# DE-140824.net
KiCad netlist of a schematic drawn in Altium Designer
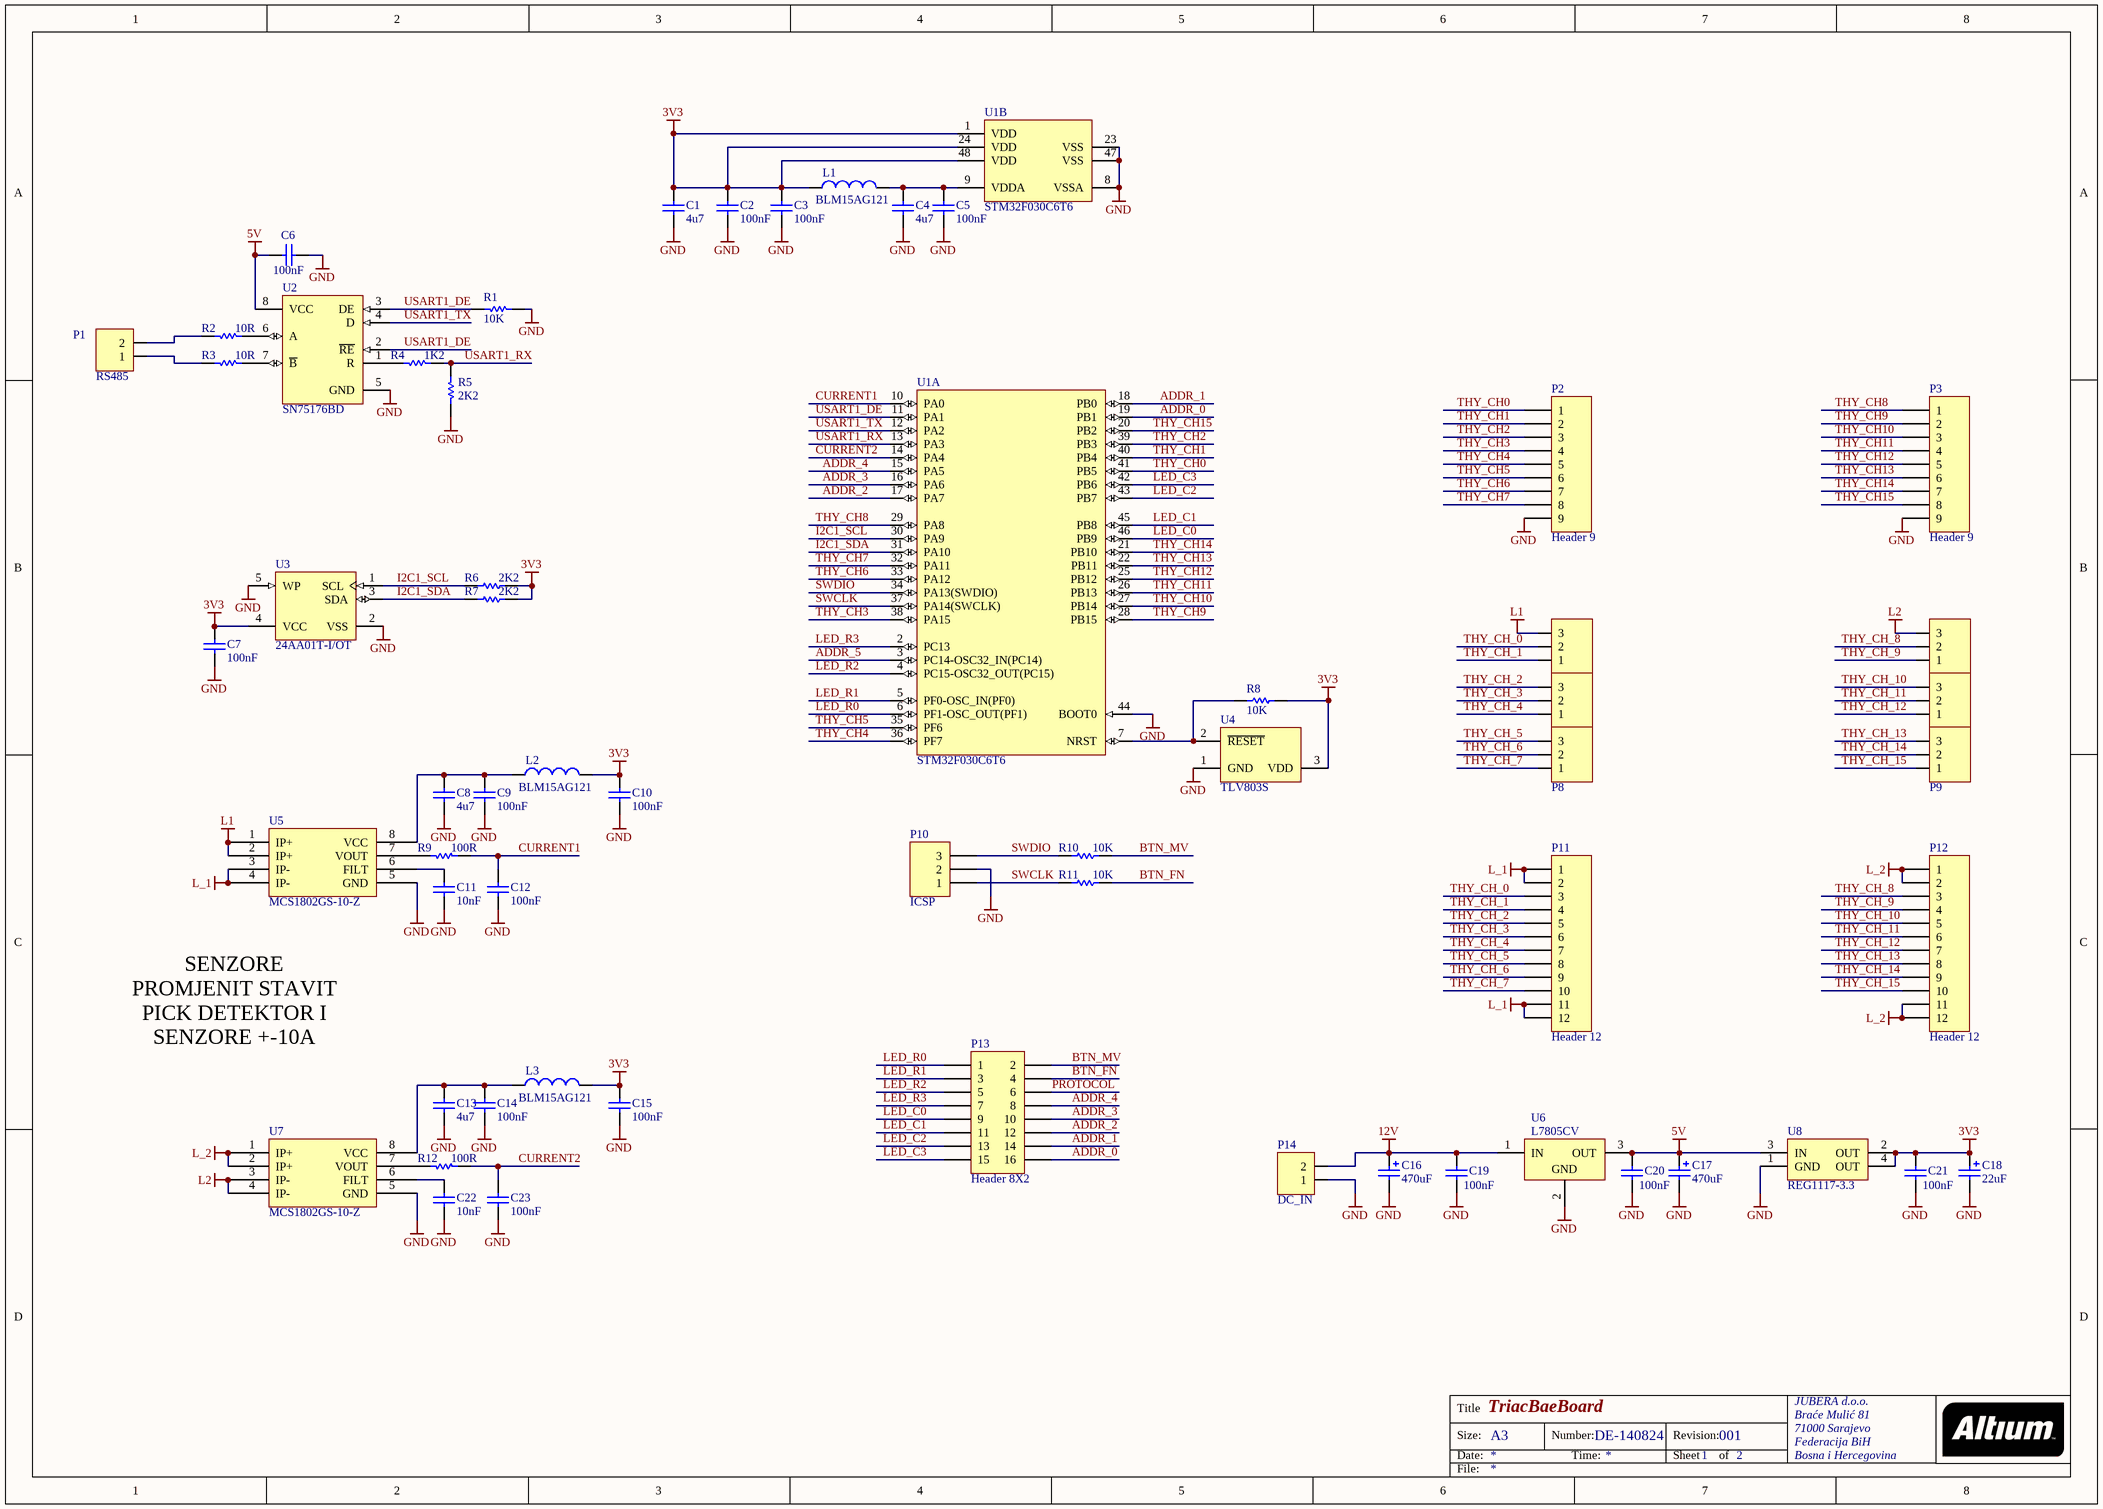
[diagram p0: DE-140824.SchDoc]

(export (version "E")
  (design (tool "Eeschema 10.0.6"))
  (components
    (comp (ref "C1")
      (value "4u7")
      (footprint "0805")
      (description "Ceramic Chip Capacitor - Standard")
      (fields (field (name "Comment") "C0805") (field (name "PUBLISHER") "Altium Limited"))
      (libsource (lib "DE-120824") (part "C0805"))
    )
    (comp (ref "C2")
      (value "100nF")
      (footprint "0603")
      (description "Ceramic Chip Capacitor - Standard")
      (fields (field (name "Comment") "C0603") (field (name "PUBLISHER") "Altium Limited"))
      (libsource (lib "DE-120824") (part "C0603"))
    )
    (comp (ref "C3")
      (value "100nF")
      (footprint "0603")
      (description "Ceramic Chip Capacitor - Standard")
      (fields (field (name "Comment") "C0603") (field (name "PUBLISHER") "Altium Limited"))
      (libsource (lib "DE-120824") (part "C0603"))
    )
    (comp (ref "C4")
      (value "4u7")
      (footprint "0805")
      (description "Ceramic Chip Capacitor - Standard")
      (fields (field (name "Comment") "C0805") (field (name "PUBLISHER") "Altium Limited"))
      (libsource (lib "DE-120824") (part "C0805"))
    )
    (comp (ref "C5")
      (value "100nF")
      (footprint "0603")
      (description "Ceramic Chip Capacitor - Standard")
      (fields (field (name "Comment") "C0603") (field (name "PUBLISHER") "Altium Limited"))
      (libsource (lib "DE-120824") (part "C0603"))
    )
    (comp (ref "C6")
      (value "100nF")
      (footprint "0603")
      (description "Ceramic Chip Capacitor - Standard")
      (fields (field (name "PUBLISHER") "Altium Limited"))
      (libsource (lib "DE-220817") (part "C0603"))
    )
    (comp (ref "C7")
      (value "100nF")
      (footprint "0603")
      (description "Ceramic Chip Capacitor - Standard")
      (fields (field (name "Comment") "C0603") (field (name "PUBLISHER") "Altium Limited"))
      (libsource (lib "DE-120824") (part "C0603"))
    )
    (comp (ref "C8")
      (value "4u7")
      (footprint "0805")
      (description "Ceramic Chip Capacitor - Standard")
      (fields (field (name "Comment") "C0805") (field (name "PUBLISHER") "Altium Limited"))
      (libsource (lib "DE-120824") (part "C0805"))
    )
    (comp (ref "C9")
      (value "100nF")
      (footprint "0603")
      (description "Ceramic Chip Capacitor - Standard")
      (fields (field (name "Comment") "C0603") (field (name "PUBLISHER") "Altium Limited"))
      (libsource (lib "DE-120824") (part "C0603"))
    )
    (comp (ref "C10")
      (value "100nF")
      (footprint "0603")
      (description "Ceramic Chip Capacitor - Standard")
      (fields (field (name "Comment") "C0603") (field (name "PUBLISHER") "Altium Limited"))
      (libsource (lib "DE-120824") (part "C0603"))
    )
    (comp (ref "C11")
      (value "10nF")
      (footprint "0603")
      (description "Ceramic Chip Capacitor - Standard")
      (fields (field (name "Comment") "C0603") (field (name "PUBLISHER") "Altium Limited"))
      (libsource (lib "DE-120824") (part "C0603"))
    )
    (comp (ref "C12")
      (value "100nF")
      (footprint "0603")
      (description "Ceramic Chip Capacitor - Standard")
      (fields (field (name "Comment") "C0603") (field (name "PUBLISHER") "Altium Limited"))
      (libsource (lib "DE-120824") (part "C0603"))
    )
    (comp (ref "C13")
      (value "4u7")
      (footprint "0805")
      (description "Ceramic Chip Capacitor - Standard")
      (fields (field (name "Comment") "C0805") (field (name "PUBLISHER") "Altium Limited"))
      (libsource (lib "DE-120824") (part "C0805"))
    )
    (comp (ref "C14")
      (value "100nF")
      (footprint "0603")
      (description "Ceramic Chip Capacitor - Standard")
      (fields (field (name "Comment") "C0603") (field (name "PUBLISHER") "Altium Limited"))
      (libsource (lib "DE-120824") (part "C0603"))
    )
    (comp (ref "C15")
      (value "100nF")
      (footprint "0603")
      (description "Ceramic Chip Capacitor - Standard")
      (fields (field (name "Comment") "C0603") (field (name "PUBLISHER") "Altium Limited"))
      (libsource (lib "DE-120824") (part "C0603"))
    )
    (comp (ref "C16")
      (value "470uF")
      (footprint "CAPPR5-10X12.5")
      (description "Aluminum Electrolytic Capacitor, Radial Style with Long Leads: 470uF, 25V")
      (fields (field (name "PUBLISHER") "Altium Limited"))
      (libsource (lib "DE-010824") (part "EKA00DC347E00"))
    )
    (comp (ref "C17")
      (value "470uF")
      (footprint "CAPPR5-10X12.5")
      (description "Aluminum Electrolytic Capacitor, Radial Style with Long Leads: 470uF, 25V")
      (fields (field (name "PUBLISHER") "Altium Limited"))
      (libsource (lib "DE-010824") (part "EKA00DC347E00"))
    )
    (comp (ref "C18")
      (value "22uF")
      (footprint "CAPPR2-5X11")
      (description "Aluminum Electrolytic Capacitor, Radial Style with Long Leads: 47uF, 35V")
      (fields (field (name "PUBLISHER") "Altium Limited"))
      (libsource (lib "DE-010824") (part "EKA00AA247F00"))
    )
    (comp (ref "C19")
      (value "100nF")
      (footprint "0603")
      (description "Ceramic Chip Capacitor - Standard")
      (fields (field (name "PUBLISHER") "Altium Limited"))
      (libsource (lib "DE-220817") (part "C0603"))
    )
    (comp (ref "C20")
      (value "100nF")
      (footprint "0603")
      (description "Ceramic Chip Capacitor - Standard")
      (fields (field (name "PUBLISHER") "Altium Limited"))
      (libsource (lib "DE-220817") (part "C0603"))
    )
    (comp (ref "C21")
      (value "100nF")
      (footprint "0603")
      (description "Ceramic Chip Capacitor - Standard")
      (fields (field (name "PUBLISHER") "Altium Limited"))
      (libsource (lib "DE-220817") (part "C0603"))
    )
    (comp (ref "C22")
      (value "10nF")
      (footprint "0603")
      (description "Ceramic Chip Capacitor - Standard")
      (fields (field (name "Comment") "C0603") (field (name "PUBLISHER") "Altium Limited"))
      (libsource (lib "DE-120824") (part "C0603"))
    )
    (comp (ref "C23")
      (value "100nF")
      (footprint "0603")
      (description "Ceramic Chip Capacitor - Standard")
      (fields (field (name "Comment") "C0603") (field (name "PUBLISHER") "Altium Limited"))
      (libsource (lib "DE-120824") (part "C0603"))
    )
    (comp (ref "L1")
      (value "BLM15AG121")
      (footprint "0402-A")
      (description "SMD chip inductor")
      (fields (field (name "PUBLISHER") "Altium Limited"))
      (libsource (lib "DE-120824") (part "Chip inductor"))
    )
    (comp (ref "L2")
      (value "BLM15AG121")
      (footprint "0402-A")
      (description "SMD chip inductor")
      (fields (field (name "PUBLISHER") "Altium Limited"))
      (libsource (lib "DE-120824") (part "Chip inductor"))
    )
    (comp (ref "L3")
      (value "BLM15AG121")
      (footprint "0402-A")
      (description "SMD chip inductor")
      (fields (field (name "PUBLISHER") "Altium Limited"))
      (libsource (lib "DE-120824") (part "Chip inductor"))
    )
    (comp (ref "P1")
      (value "RS485")
      (footprint "TERMINAL BLOK 2")
      (description "Terminal blok konektor 3,5 mm")
      (libsource (lib "DE-120824") (part "TERMINAL BLOK 2"))
    )
    (comp (ref "P2")
      (value "Header 9")
      (footprint "HDR1X9")
      (description "Header, 9-Pin")
      (fields (field (name "PUBLISHER") "Altium Limited"))
      (libsource (lib "Miscellaneous Connectors") (part "Header 9"))
    )
    (comp (ref "P3")
      (value "Header 9")
      (footprint "HDR1X9")
      (description "Header, 9-Pin")
      (fields (field (name "PUBLISHER") "Altium Limited"))
      (libsource (lib "Miscellaneous Connectors") (part "Header 9"))
    )
    (comp (ref "P4")
      (value "~")
      (footprint "TERMINAL BLOK 3")
      (description "3 pinski terminal blok konektor")
      (libsource (lib "DE-120824") (part "TERMINAL BLOK 3"))
    )
    (comp (ref "P5")
      (value "~")
      (footprint "TERMINAL BLOK 3")
      (description "3 pinski terminal blok konektor")
      (libsource (lib "DE-120824") (part "TERMINAL BLOK 3"))
    )
    (comp (ref "P6")
      (value "~")
      (footprint "TERMINAL BLOK 3")
      (description "3 pinski terminal blok konektor")
      (libsource (lib "DE-120824") (part "TERMINAL BLOK 3"))
    )
    (comp (ref "P7")
      (value "~")
      (footprint "TERMINAL BLOK 3")
      (description "3 pinski terminal blok konektor")
      (libsource (lib "DE-120824") (part "TERMINAL BLOK 3"))
    )
    (comp (ref "P8")
      (value "~")
      (footprint "TERMINAL BLOK 3")
      (description "3 pinski terminal blok konektor")
      (libsource (lib "DE-120824") (part "TERMINAL BLOK 3"))
    )
    (comp (ref "P9")
      (value "~")
      (footprint "TERMINAL BLOK 3")
      (description "3 pinski terminal blok konektor")
      (libsource (lib "DE-120824") (part "TERMINAL BLOK 3"))
    )
    (comp (ref "P10")
      (value "ICSP")
      (footprint "HDR1X3")
      (description "Header, 3-Pin")
      (fields (field (name "PUBLISHER") "Altium Limited"))
      (libsource (lib "Miscellaneous Connectors") (part "Header 3"))
    )
    (comp (ref "P11")
      (value "Header 12")
      (footprint "HDR1X12")
      (description "Header, 12-Pin")
      (fields (field (name "PUBLISHER") "Altium Limited"))
      (libsource (lib "Miscellaneous Connectors") (part "Header 12"))
    )
    (comp (ref "P12")
      (value "Header 12")
      (footprint "HDR1X12")
      (description "Header, 12-Pin")
      (fields (field (name "PUBLISHER") "Altium Limited"))
      (libsource (lib "Miscellaneous Connectors") (part "Header 12"))
    )
    (comp (ref "P13")
      (value "Header 8X2")
      (footprint "HDR2X8")
      (description "Header, 8-Pin, Dual row")
      (fields (field (name "PUBLISHER") "Altium Limited"))
      (libsource (lib "Miscellaneous Connectors") (part "Header 8X2"))
    )
    (comp (ref "P14")
      (value "DC_IN")
      (footprint "TERMINAL BLOK 2")
      (description "Terminal blok konektor 3,5 mm")
      (libsource (lib "DE-010824") (part "TERMINAL BLOK 2"))
    )
    (comp (ref "R1")
      (value "10K")
      (footprint "ERA-0603")
      (fields (field (name "PUBLISHER") "Altium Limited"))
      (libsource (lib "DE-220817") (part "ERAV"))
    )
    (comp (ref "R2")
      (value "10R")
      (footprint "ERA-0603")
      (fields (field (name "PUBLISHER") "Altium Limited"))
      (libsource (lib "DE-220817") (part "ERAV"))
    )
    (comp (ref "R3")
      (value "10R")
      (footprint "ERA-0603")
      (fields (field (name "PUBLISHER") "Altium Limited"))
      (libsource (lib "DE-220817") (part "ERAV"))
    )
    (comp (ref "R4")
      (value "1K2")
      (footprint "ERA-0603")
      (fields (field (name "PUBLISHER") "Altium Limited"))
      (libsource (lib "DE-220817") (part "ERAV"))
    )
    (comp (ref "R5")
      (value "2K2")
      (footprint "ERA-0603")
      (fields (field (name "PUBLISHER") "Altium Limited"))
      (libsource (lib "DE-220817") (part "ERAV"))
    )
    (comp (ref "R6")
      (value "2K2")
      (footprint "ERA-0603")
      (fields (field (name "PUBLISHER") "Altium Limited"))
      (libsource (lib "DE-120824") (part "ERA3Y"))
    )
    (comp (ref "R7")
      (value "2K2")
      (footprint "ERA-0603")
      (fields (field (name "PUBLISHER") "Altium Limited"))
      (libsource (lib "DE-120824") (part "ERA3Y"))
    )
    (comp (ref "R8")
      (value "10K")
      (footprint "ERA-0603")
      (fields (field (name "PUBLISHER") "Altium Limited"))
      (libsource (lib "DE-120824") (part "ERA3Y"))
    )
    (comp (ref "R9")
      (value "100R")
      (footprint "ERA-0603")
      (fields (field (name "PUBLISHER") "Altium Limited"))
      (libsource (lib "DE-220817") (part "ERAV"))
    )
    (comp (ref "R10")
      (value "10K")
      (footprint "ERA-0603")
      (fields (field (name "PUBLISHER") "Altium Limited"))
      (libsource (lib "DE-120824") (part "ERA3Y"))
    )
    (comp (ref "R11")
      (value "10K")
      (footprint "ERA-0603")
      (fields (field (name "PUBLISHER") "Altium Limited"))
      (libsource (lib "DE-120824") (part "ERA3Y"))
    )
    (comp (ref "R12")
      (value "100R")
      (footprint "ERA-0603")
      (fields (field (name "PUBLISHER") "Altium Limited"))
      (libsource (lib "DE-220817") (part "ERAV"))
    )
    (comp (ref "U1")
      (value "STM32F030C6T6")
      (footprint "STM-LQFP48_N")
      (libsource (lib "STMicroelectronics STM32 F0") (part "STM32F030C6T6"))
    )
    (comp (ref "U2")
      (value "SN75176BD")
      (footprint "D008_N")
      (description "Differential Bus Transceiver")
      (fields (field (name "PUBLISHER") "Altium Limited"))
      (libsource (lib "DE-010824") (part "SN75176BD"))
    )
    (comp (ref "U3")
      (value "24AA01T-I/OT")
      (footprint "SOT-23-OT5_N")
      (description "1Kbit, 400kHz, 1.8V, I2C Serial EEPROM, 5-Pin SOT-23, Industrial Temperature, Tape and Reel")
      (fields (field (name "PUBLISHER") "Altium Limited"))
      (libsource (lib "Microchip Memory I2C Serial EEPROM") (part "24AA01T-I/OT"))
    )
    (comp (ref "U4")
      (value "TLV803S")
      (footprint "DBZ3_N")
      (fields (field (name "MANUFACTURER") "Texas Instruments") (field (name "PARTNUMBER") "TLV803MDBZR"))
      (libsource (lib "TI Power Management Supervisor and Reset IC") (part "TLV803MDBZR"))
    )
    (comp (ref "U5")
      (value "MCS1802GS-10-Z")
      (footprint "SOIC-SN8_N")
      (libsource (lib "DE-120824") (part "ACS71240"))
    )
    (comp (ref "U6")
      (value "L7805CV")
      (footprint "TO220")
      (description "Positive Voltage Regulator, 5V, 3-Pin TO-220")
      (libsource (lib "DE-010824") (part "L7805CV"))
    )
    (comp (ref "U7")
      (value "MCS1802GS-10-Z")
      (footprint "SOIC-SN8_N")
      (libsource (lib "DE-120824") (part "ACS71240"))
    )
    (comp (ref "U8")
      (value "REG1117-3.3")
      (footprint "ZZ311")
      (description "800mA and 1A Low Dropout Positive Regulator 2.85V, 3.3V, 5V, and Adjustable")
      (fields (field (name "PUBLISHER") "Altium Limited"))
      (libsource (lib "DE-010824") (part "REG1117-3.3"))
    )
  )
  (nets
    (net (code "1") (name "/ADDR_0") (class "Default")
      (node (ref "P13") (pin "16") (pinfunction "16_16") (pintype "passive"))
      (node (ref "U1") (pin "19") (pinfunction "PB1_19") (pintype "bidirectional"))
    )
    (net (code "2") (name "/ADDR_1") (class "Default")
      (node (ref "P13") (pin "14") (pinfunction "14_14") (pintype "passive"))
      (node (ref "U1") (pin "18") (pinfunction "PB0_18") (pintype "bidirectional"))
    )
    (net (code "3") (name "/ADDR_2") (class "Default")
      (node (ref "P13") (pin "12") (pinfunction "12_12") (pintype "passive"))
      (node (ref "U1") (pin "17") (pinfunction "PA7_17") (pintype "bidirectional"))
    )
    (net (code "4") (name "/ADDR_3") (class "Default")
      (node (ref "P13") (pin "10") (pinfunction "10_10") (pintype "passive"))
      (node (ref "U1") (pin "16") (pinfunction "PA6_16") (pintype "bidirectional"))
    )
    (net (code "5") (name "/ADDR_4") (class "Default")
      (node (ref "P13") (pin "8") (pinfunction "8_8") (pintype "passive"))
      (node (ref "U1") (pin "15") (pinfunction "PA5_15") (pintype "bidirectional"))
    )
    (net (code "6") (name "/ADDR_5") (class "Default")
      (node (ref "U1") (pin "3") (pinfunction "PC14-OSC32_IN(PC14)_3") (pintype "bidirectional"))
    )
    (net (code "7") (name "/BTN_FN") (class "Default")
      (node (ref "P13") (pin "4") (pinfunction "4_4") (pintype "passive"))
      (node (ref "R11") (pin "2") (pinfunction "2_2") (pintype "passive"))
    )
    (net (code "8") (name "/BTN_MV") (class "Default")
      (node (ref "P13") (pin "2") (pinfunction "2_2") (pintype "passive"))
      (node (ref "R10") (pin "2") (pinfunction "2_2") (pintype "passive"))
    )
    (net (code "9") (name "/CURRENT1") (class "Default")
      (node (ref "C12") (pin "2") (pinfunction "2_2") (pintype "passive"))
      (node (ref "R9") (pin "1") (pinfunction "1_1") (pintype "passive"))
      (node (ref "U1") (pin "10") (pinfunction "PA0_10") (pintype "bidirectional"))
    )
    (net (code "10") (name "/CURRENT2") (class "Default")
      (node (ref "C23") (pin "2") (pinfunction "2_2") (pintype "passive"))
      (node (ref "R12") (pin "1") (pinfunction "1_1") (pintype "passive"))
      (node (ref "U1") (pin "14") (pinfunction "PA4_14") (pintype "bidirectional"))
    )
    (net (code "11") (name "/I2C1_SCL") (class "Default")
      (node (ref "R6") (pin "1") (pinfunction "1_1") (pintype "passive"))
      (node (ref "U1") (pin "30") (pinfunction "PA9_30") (pintype "bidirectional"))
      (node (ref "U3") (pin "1") (pinfunction "SCL_1") (pintype "input"))
    )
    (net (code "12") (name "/I2C1_SDA") (class "Default")
      (node (ref "R7") (pin "1") (pinfunction "1_1") (pintype "passive"))
      (node (ref "U1") (pin "31") (pinfunction "PA10_31") (pintype "bidirectional"))
      (node (ref "U3") (pin "3") (pinfunction "SDA_3") (pintype "bidirectional"))
    )
    (net (code "13") (name "/LED_C0") (class "Default")
      (node (ref "P13") (pin "9") (pinfunction "9_9") (pintype "passive"))
      (node (ref "U1") (pin "46") (pinfunction "PB9_46") (pintype "bidirectional"))
    )
    (net (code "14") (name "/LED_C1") (class "Default")
      (node (ref "P13") (pin "11") (pinfunction "11_11") (pintype "passive"))
      (node (ref "U1") (pin "45") (pinfunction "PB8_45") (pintype "bidirectional"))
    )
    (net (code "15") (name "/LED_C2") (class "Default")
      (node (ref "P13") (pin "13") (pinfunction "13_13") (pintype "passive"))
      (node (ref "U1") (pin "43") (pinfunction "PB7_43") (pintype "bidirectional"))
    )
    (net (code "16") (name "/LED_C3") (class "Default")
      (node (ref "P13") (pin "15") (pinfunction "15_15") (pintype "passive"))
      (node (ref "U1") (pin "42") (pinfunction "PB6_42") (pintype "bidirectional"))
    )
    (net (code "17") (name "/LED_R0") (class "Default")
      (node (ref "P13") (pin "1") (pinfunction "1_1") (pintype "passive"))
      (node (ref "U1") (pin "6") (pinfunction "PF1-OSC_OUT(PF1)_6") (pintype "bidirectional"))
    )
    (net (code "18") (name "/LED_R1") (class "Default")
      (node (ref "P13") (pin "3") (pinfunction "3_3") (pintype "passive"))
      (node (ref "U1") (pin "5") (pinfunction "PF0-OSC_IN(PF0)_5") (pintype "bidirectional"))
    )
    (net (code "19") (name "/LED_R2") (class "Default")
      (node (ref "P13") (pin "5") (pinfunction "5_5") (pintype "passive"))
      (node (ref "U1") (pin "4") (pinfunction "PC15-OSC32_OUT(PC15)_4") (pintype "bidirectional"))
    )
    (net (code "20") (name "/LED_R3") (class "Default")
      (node (ref "P13") (pin "7") (pinfunction "7_7") (pintype "passive"))
      (node (ref "U1") (pin "2") (pinfunction "PC13_2") (pintype "bidirectional"))
    )
    (net (code "21") (name "/PROTOCOL") (class "Default")
      (node (ref "P13") (pin "6") (pinfunction "6_6") (pintype "passive"))
    )
    (net (code "22") (name "/SWCLK") (class "Default")
      (node (ref "P10") (pin "1") (pinfunction "1_1") (pintype "passive"))
      (node (ref "R11") (pin "1") (pinfunction "1_1") (pintype "passive"))
      (node (ref "U1") (pin "37") (pinfunction "PA14(SWCLK)_37") (pintype "bidirectional"))
    )
    (net (code "23") (name "/SWDIO") (class "Default")
      (node (ref "P10") (pin "3") (pinfunction "3_3") (pintype "passive"))
      (node (ref "R10") (pin "1") (pinfunction "1_1") (pintype "passive"))
      (node (ref "U1") (pin "34") (pinfunction "PA13(SWDIO)_34") (pintype "bidirectional"))
    )
    (net (code "24") (name "/THY_CH0") (class "Default")
      (node (ref "P2") (pin "1") (pinfunction "1_1") (pintype "passive"))
      (node (ref "U1") (pin "41") (pinfunction "PB5_41") (pintype "bidirectional"))
    )
    (net (code "25") (name "/THY_CH1") (class "Default")
      (node (ref "P2") (pin "2") (pinfunction "2_2") (pintype "passive"))
      (node (ref "U1") (pin "40") (pinfunction "PB4_40") (pintype "bidirectional"))
    )
    (net (code "26") (name "/THY_CH2") (class "Default")
      (node (ref "P2") (pin "3") (pinfunction "3_3") (pintype "passive"))
      (node (ref "U1") (pin "39") (pinfunction "PB3_39") (pintype "bidirectional"))
    )
    (net (code "27") (name "/THY_CH3") (class "Default")
      (node (ref "P2") (pin "4") (pinfunction "4_4") (pintype "passive"))
      (node (ref "U1") (pin "38") (pinfunction "PA15_38") (pintype "bidirectional"))
    )
    (net (code "28") (name "/THY_CH4") (class "Default")
      (node (ref "P2") (pin "5") (pinfunction "5_5") (pintype "passive"))
      (node (ref "U1") (pin "36") (pinfunction "PF7_36") (pintype "bidirectional"))
    )
    (net (code "29") (name "/THY_CH5") (class "Default")
      (node (ref "P2") (pin "6") (pinfunction "6_6") (pintype "passive"))
      (node (ref "U1") (pin "35") (pinfunction "PF6_35") (pintype "bidirectional"))
    )
    (net (code "30") (name "/THY_CH6") (class "Default")
      (node (ref "P2") (pin "7") (pinfunction "7_7") (pintype "passive"))
      (node (ref "U1") (pin "33") (pinfunction "PA12_33") (pintype "bidirectional"))
    )
    (net (code "31") (name "/THY_CH7") (class "Default")
      (node (ref "P2") (pin "8") (pinfunction "8_8") (pintype "passive"))
      (node (ref "U1") (pin "32") (pinfunction "PA11_32") (pintype "bidirectional"))
    )
    (net (code "32") (name "/THY_CH8") (class "Default")
      (node (ref "P3") (pin "1") (pinfunction "1_1") (pintype "passive"))
      (node (ref "U1") (pin "29") (pinfunction "PA8_29") (pintype "bidirectional"))
    )
    (net (code "33") (name "/THY_CH9") (class "Default")
      (node (ref "P3") (pin "2") (pinfunction "2_2") (pintype "passive"))
      (node (ref "U1") (pin "28") (pinfunction "PB15_28") (pintype "bidirectional"))
    )
    (net (code "34") (name "/THY_CH10") (class "Default")
      (node (ref "P3") (pin "3") (pinfunction "3_3") (pintype "passive"))
      (node (ref "U1") (pin "27") (pinfunction "PB14_27") (pintype "bidirectional"))
    )
    (net (code "35") (name "/THY_CH11") (class "Default")
      (node (ref "P3") (pin "4") (pinfunction "4_4") (pintype "passive"))
      (node (ref "U1") (pin "26") (pinfunction "PB13_26") (pintype "bidirectional"))
    )
    (net (code "36") (name "/THY_CH12") (class "Default")
      (node (ref "P3") (pin "5") (pinfunction "5_5") (pintype "passive"))
      (node (ref "U1") (pin "25") (pinfunction "PB12_25") (pintype "bidirectional"))
    )
    (net (code "37") (name "/THY_CH13") (class "Default")
      (node (ref "P3") (pin "6") (pinfunction "6_6") (pintype "passive"))
      (node (ref "U1") (pin "22") (pinfunction "PB11_22") (pintype "bidirectional"))
    )
    (net (code "38") (name "/THY_CH14") (class "Default")
      (node (ref "P3") (pin "7") (pinfunction "7_7") (pintype "passive"))
      (node (ref "U1") (pin "21") (pinfunction "PB10_21") (pintype "bidirectional"))
    )
    (net (code "39") (name "/THY_CH15") (class "Default")
      (node (ref "P3") (pin "8") (pinfunction "8_8") (pintype "passive"))
      (node (ref "U1") (pin "20") (pinfunction "PB2_20") (pintype "bidirectional"))
    )
    (net (code "40") (name "/THY_CH_0") (class "Default")
      (node (ref "P11") (pin "3") (pinfunction "3_3") (pintype "passive"))
      (node (ref "P4") (pin "2") (pinfunction "2_2") (pintype "passive"))
    )
    (net (code "41") (name "/THY_CH_1") (class "Default")
      (node (ref "P11") (pin "4") (pinfunction "4_4") (pintype "passive"))
      (node (ref "P4") (pin "1") (pinfunction "1_1") (pintype "passive"))
    )
    (net (code "42") (name "/THY_CH_2") (class "Default")
      (node (ref "P11") (pin "5") (pinfunction "5_5") (pintype "passive"))
      (node (ref "P6") (pin "3") (pinfunction "3_3") (pintype "passive"))
    )
    (net (code "43") (name "/THY_CH_3") (class "Default")
      (node (ref "P11") (pin "6") (pinfunction "6_6") (pintype "passive"))
      (node (ref "P6") (pin "2") (pinfunction "2_2") (pintype "passive"))
    )
    (net (code "44") (name "/THY_CH_4") (class "Default")
      (node (ref "P11") (pin "7") (pinfunction "7_7") (pintype "passive"))
      (node (ref "P6") (pin "1") (pinfunction "1_1") (pintype "passive"))
    )
    (net (code "45") (name "/THY_CH_5") (class "Default")
      (node (ref "P11") (pin "8") (pinfunction "8_8") (pintype "passive"))
      (node (ref "P8") (pin "3") (pinfunction "3_3") (pintype "passive"))
    )
    (net (code "46") (name "/THY_CH_6") (class "Default")
      (node (ref "P11") (pin "9") (pinfunction "9_9") (pintype "passive"))
      (node (ref "P8") (pin "2") (pinfunction "2_2") (pintype "passive"))
    )
    (net (code "47") (name "/THY_CH_7") (class "Default")
      (node (ref "P11") (pin "10") (pinfunction "10_10") (pintype "passive"))
      (node (ref "P8") (pin "1") (pinfunction "1_1") (pintype "passive"))
    )
    (net (code "48") (name "/THY_CH_8") (class "Default")
      (node (ref "P12") (pin "3") (pinfunction "3_3") (pintype "passive"))
      (node (ref "P5") (pin "2") (pinfunction "2_2") (pintype "passive"))
    )
    (net (code "49") (name "/THY_CH_9") (class "Default")
      (node (ref "P12") (pin "4") (pinfunction "4_4") (pintype "passive"))
      (node (ref "P5") (pin "1") (pinfunction "1_1") (pintype "passive"))
    )
    (net (code "50") (name "/THY_CH_10") (class "Default")
      (node (ref "P12") (pin "5") (pinfunction "5_5") (pintype "passive"))
      (node (ref "P7") (pin "3") (pinfunction "3_3") (pintype "passive"))
    )
    (net (code "51") (name "/THY_CH_11") (class "Default")
      (node (ref "P12") (pin "6") (pinfunction "6_6") (pintype "passive"))
      (node (ref "P7") (pin "2") (pinfunction "2_2") (pintype "passive"))
    )
    (net (code "52") (name "/THY_CH_12") (class "Default")
      (node (ref "P12") (pin "7") (pinfunction "7_7") (pintype "passive"))
      (node (ref "P7") (pin "1") (pinfunction "1_1") (pintype "passive"))
    )
    (net (code "53") (name "/THY_CH_13") (class "Default")
      (node (ref "P12") (pin "8") (pinfunction "8_8") (pintype "passive"))
      (node (ref "P9") (pin "3") (pinfunction "3_3") (pintype "passive"))
    )
    (net (code "54") (name "/THY_CH_14") (class "Default")
      (node (ref "P12") (pin "9") (pinfunction "9_9") (pintype "passive"))
      (node (ref "P9") (pin "2") (pinfunction "2_2") (pintype "passive"))
    )
    (net (code "55") (name "/THY_CH_15") (class "Default")
      (node (ref "P12") (pin "10") (pinfunction "10_10") (pintype "passive"))
      (node (ref "P9") (pin "1") (pinfunction "1_1") (pintype "passive"))
    )
    (net (code "56") (name "/USART1_DE") (class "Default")
      (node (ref "R1") (pin "2") (pinfunction "2_2") (pintype "passive"))
      (node (ref "U1") (pin "11") (pinfunction "PA1_11") (pintype "bidirectional"))
      (node (ref "U2") (pin "2") (pinfunction "~{RE}_2") (pintype "input"))
      (node (ref "U2") (pin "3") (pinfunction "DE_3") (pintype "input"))
    )
    (net (code "57") (name "/USART1_RX") (class "Default")
      (node (ref "R4") (pin "1") (pinfunction "1_1") (pintype "passive"))
      (node (ref "R5") (pin "1") (pinfunction "1_1") (pintype "passive"))
      (node (ref "U1") (pin "13") (pinfunction "PA3_13") (pintype "bidirectional"))
    )
    (net (code "58") (name "/USART1_TX") (class "Default")
      (node (ref "U1") (pin "12") (pinfunction "PA2_12") (pintype "bidirectional"))
      (node (ref "U2") (pin "4") (pinfunction "D_4") (pintype "input"))
    )
    (net (code "59") (name "3V3") (class "Default")
      (node (ref "C1") (pin "2") (pinfunction "2_2") (pintype "passive"))
      (node (ref "C10") (pin "2") (pinfunction "2_2") (pintype "passive"))
      (node (ref "C15") (pin "2") (pinfunction "2_2") (pintype "passive"))
      (node (ref "C18") (pin "1") (pinfunction "1_1") (pintype "passive"))
      (node (ref "C2") (pin "2") (pinfunction "2_2") (pintype "passive"))
      (node (ref "C21") (pin "2") (pinfunction "2_2") (pintype "passive"))
      (node (ref "C3") (pin "2") (pinfunction "2_2") (pintype "passive"))
      (node (ref "C7") (pin "2") (pinfunction "2_2") (pintype "passive"))
      (node (ref "L1") (pin "1") (pinfunction "1_1") (pintype "passive"))
      (node (ref "L2") (pin "2") (pinfunction "2_2") (pintype "passive"))
      (node (ref "L3") (pin "2") (pinfunction "2_2") (pintype "passive"))
      (node (ref "R6") (pin "2") (pinfunction "2_2") (pintype "passive"))
      (node (ref "R7") (pin "2") (pinfunction "2_2") (pintype "passive"))
      (node (ref "R8") (pin "2") (pinfunction "2_2") (pintype "passive"))
      (node (ref "U1") (pin "1") (pinfunction "VDD_1") (pintype "power_in"))
      (node (ref "U1") (pin "24") (pinfunction "VDD_24") (pintype "power_in"))
      (node (ref "U1") (pin "48") (pinfunction "VDD_48") (pintype "power_in"))
      (node (ref "U3") (pin "4") (pinfunction "VCC_4") (pintype "power_in"))
      (node (ref "U4") (pin "3") (pinfunction "VDD_3") (pintype "power_in"))
      (node (ref "U8") (pin "2") (pinfunction "OUT_2") (pintype "power_in"))
      (node (ref "U8") (pin "4") (pinfunction "OUT_4") (pintype "power_in"))
    )
    (net (code "60") (name "5V") (class "Default")
      (node (ref "C17") (pin "1") (pinfunction "1_1") (pintype "passive"))
      (node (ref "C20") (pin "2") (pinfunction "2_2") (pintype "passive"))
      (node (ref "C6") (pin "1") (pinfunction "1_1") (pintype "passive"))
      (node (ref "U2") (pin "8") (pinfunction "VCC_8") (pintype "power_in"))
      (node (ref "U6") (pin "3") (pinfunction "OUT_3") (pintype "power_in"))
      (node (ref "U8") (pin "3") (pinfunction "IN_3") (pintype "power_in"))
    )
    (net (code "61") (name "12V") (class "Default")
      (node (ref "C16") (pin "1") (pinfunction "1_1") (pintype "passive"))
      (node (ref "C19") (pin "2") (pinfunction "2_2") (pintype "passive"))
      (node (ref "P14") (pin "2") (pinfunction "2_2") (pintype "passive"))
      (node (ref "U6") (pin "1") (pinfunction "IN_1") (pintype "power_in"))
    )
    (net (code "62") (name "GND") (class "Default")
      (node (ref "C1") (pin "1") (pinfunction "1_1") (pintype "passive"))
      (node (ref "C10") (pin "1") (pinfunction "1_1") (pintype "passive"))
      (node (ref "C11") (pin "1") (pinfunction "1_1") (pintype "passive"))
      (node (ref "C12") (pin "1") (pinfunction "1_1") (pintype "passive"))
      (node (ref "C13") (pin "1") (pinfunction "1_1") (pintype "passive"))
      (node (ref "C14") (pin "1") (pinfunction "1_1") (pintype "passive"))
      (node (ref "C15") (pin "1") (pinfunction "1_1") (pintype "passive"))
      (node (ref "C16") (pin "2") (pinfunction "2_2") (pintype "passive"))
      (node (ref "C17") (pin "2") (pinfunction "2_2") (pintype "passive"))
      (node (ref "C18") (pin "2") (pinfunction "2_2") (pintype "passive"))
      (node (ref "C19") (pin "1") (pinfunction "1_1") (pintype "passive"))
      (node (ref "C2") (pin "1") (pinfunction "1_1") (pintype "passive"))
      (node (ref "C20") (pin "1") (pinfunction "1_1") (pintype "passive"))
      (node (ref "C21") (pin "1") (pinfunction "1_1") (pintype "passive"))
      (node (ref "C22") (pin "1") (pinfunction "1_1") (pintype "passive"))
      (node (ref "C23") (pin "1") (pinfunction "1_1") (pintype "passive"))
      (node (ref "C3") (pin "1") (pinfunction "1_1") (pintype "passive"))
      (node (ref "C4") (pin "1") (pinfunction "1_1") (pintype "passive"))
      (node (ref "C5") (pin "1") (pinfunction "1_1") (pintype "passive"))
      (node (ref "C6") (pin "2") (pinfunction "2_2") (pintype "passive"))
      (node (ref "C7") (pin "1") (pinfunction "1_1") (pintype "passive"))
      (node (ref "C8") (pin "1") (pinfunction "1_1") (pintype "passive"))
      (node (ref "C9") (pin "1") (pinfunction "1_1") (pintype "passive"))
      (node (ref "P10") (pin "2") (pinfunction "2_2") (pintype "passive"))
      (node (ref "P14") (pin "1") (pinfunction "1_1") (pintype "passive"))
      (node (ref "P2") (pin "9") (pinfunction "9_9") (pintype "passive"))
      (node (ref "P3") (pin "9") (pinfunction "9_9") (pintype "passive"))
      (node (ref "R1") (pin "1") (pinfunction "1_1") (pintype "passive"))
      (node (ref "R5") (pin "2") (pinfunction "2_2") (pintype "passive"))
      (node (ref "U1") (pin "23") (pinfunction "VSS_23") (pintype "power_in"))
      (node (ref "U1") (pin "44") (pinfunction "BOOT0_44") (pintype "input"))
      (node (ref "U1") (pin "47") (pinfunction "VSS_47") (pintype "power_in"))
      (node (ref "U1") (pin "8") (pinfunction "VSSA_8") (pintype "power_in"))
      (node (ref "U2") (pin "5") (pinfunction "GND_5") (pintype "power_in"))
      (node (ref "U3") (pin "2") (pinfunction "VSS_2") (pintype "power_in"))
      (node (ref "U3") (pin "5") (pinfunction "WP_5") (pintype "input"))
      (node (ref "U4") (pin "1") (pinfunction "GND_1") (pintype "power_in"))
      (node (ref "U5") (pin "5") (pinfunction "GND_5") (pintype "passive"))
      (node (ref "U6") (pin "2") (pinfunction "GND_2") (pintype "power_in"))
      (node (ref "U7") (pin "5") (pinfunction "GND_5") (pintype "passive"))
      (node (ref "U8") (pin "1") (pinfunction "GND_1") (pintype "power_in"))
    )
    (net (code "63") (name "L1") (class "Default")
      (node (ref "P4") (pin "3") (pinfunction "3_3") (pintype "passive"))
      (node (ref "U5") (pin "1") (pinfunction "IP+_1") (pintype "passive"))
      (node (ref "U5") (pin "2") (pinfunction "IP+_2") (pintype "passive"))
    )
    (net (code "64") (name "L2") (class "Default")
      (node (ref "P5") (pin "3") (pinfunction "3_3") (pintype "passive"))
      (node (ref "U7") (pin "3") (pinfunction "IP-_3") (pintype "passive"))
      (node (ref "U7") (pin "4") (pinfunction "IP-_4") (pintype "passive"))
    )
    (net (code "65") (name "L_1") (class "Default")
      (node (ref "P11") (pin "1") (pinfunction "1_1") (pintype "passive"))
      (node (ref "P11") (pin "11") (pinfunction "11_11") (pintype "passive"))
      (node (ref "P11") (pin "12") (pinfunction "12_12") (pintype "passive"))
      (node (ref "P11") (pin "2") (pinfunction "2_2") (pintype "passive"))
      (node (ref "U5") (pin "3") (pinfunction "IP-_3") (pintype "passive"))
      (node (ref "U5") (pin "4") (pinfunction "IP-_4") (pintype "passive"))
    )
    (net (code "66") (name "L_2") (class "Default")
      (node (ref "P12") (pin "1") (pinfunction "1_1") (pintype "passive"))
      (node (ref "P12") (pin "11") (pinfunction "11_11") (pintype "passive"))
      (node (ref "P12") (pin "12") (pinfunction "12_12") (pintype "passive"))
      (node (ref "P12") (pin "2") (pinfunction "2_2") (pintype "passive"))
      (node (ref "U7") (pin "1") (pinfunction "IP+_1") (pintype "passive"))
      (node (ref "U7") (pin "2") (pinfunction "IP+_2") (pintype "passive"))
    )
    (net (code "67") (name "Net-(P1-Pad1)") (class "Default")
      (node (ref "P1") (pin "1") (pinfunction "1_1") (pintype "passive"))
      (node (ref "R3") (pin "1") (pinfunction "1_1") (pintype "passive"))
    )
    (net (code "68") (name "Net-(P1-Pad2)") (class "Default")
      (node (ref "P1") (pin "2") (pinfunction "2_2") (pintype "passive"))
      (node (ref "R2") (pin "1") (pinfunction "1_1") (pintype "passive"))
    )
    (net (code "69") (name "Net-(U1A-NRST)") (class "Default")
      (node (ref "R8") (pin "1") (pinfunction "1_1") (pintype "passive"))
      (node (ref "U1") (pin "7") (pinfunction "NRST_7") (pintype "bidirectional"))
      (node (ref "U4") (pin "2") (pinfunction "~{RESET}_2") (pintype "open_collector"))
    )
    (net (code "70") (name "Net-(U1B-VDDA)") (class "Default")
      (node (ref "C4") (pin "2") (pinfunction "2_2") (pintype "passive"))
      (node (ref "C5") (pin "2") (pinfunction "2_2") (pintype "passive"))
      (node (ref "L1") (pin "2") (pinfunction "2_2") (pintype "passive"))
      (node (ref "U1") (pin "9") (pinfunction "VDDA_9") (pintype "power_in"))
    )
    (net (code "71") (name "Net-(U2-A)") (class "Default")
      (node (ref "R2") (pin "2") (pinfunction "2_2") (pintype "passive"))
      (node (ref "U2") (pin "6") (pinfunction "A_6") (pintype "bidirectional"))
    )
    (net (code "72") (name "Net-(U2-R)") (class "Default")
      (node (ref "R4") (pin "2") (pinfunction "2_2") (pintype "passive"))
      (node (ref "U2") (pin "1") (pinfunction "R_1") (pintype "tri_state"))
    )
    (net (code "73") (name "Net-(U2-~{B})") (class "Default")
      (node (ref "R3") (pin "2") (pinfunction "2_2") (pintype "passive"))
      (node (ref "U2") (pin "7") (pinfunction "~{B}_7") (pintype "bidirectional"))
    )
    (net (code "74") (name "Net-(U5-FILT)") (class "Default")
      (node (ref "C11") (pin "2") (pinfunction "2_2") (pintype "passive"))
      (node (ref "U5") (pin "6") (pinfunction "FILT_6") (pintype "passive"))
    )
    (net (code "75") (name "Net-(U5-VCC)") (class "Default")
      (node (ref "C8") (pin "2") (pinfunction "2_2") (pintype "passive"))
      (node (ref "C9") (pin "2") (pinfunction "2_2") (pintype "passive"))
      (node (ref "L2") (pin "1") (pinfunction "1_1") (pintype "passive"))
      (node (ref "U5") (pin "8") (pinfunction "VCC_8") (pintype "passive"))
    )
    (net (code "76") (name "Net-(U5-VOUT)") (class "Default")
      (node (ref "R9") (pin "2") (pinfunction "2_2") (pintype "passive"))
      (node (ref "U5") (pin "7") (pinfunction "VOUT_7") (pintype "passive"))
    )
    (net (code "77") (name "Net-(U7-FILT)") (class "Default")
      (node (ref "C22") (pin "2") (pinfunction "2_2") (pintype "passive"))
      (node (ref "U7") (pin "6") (pinfunction "FILT_6") (pintype "passive"))
    )
    (net (code "78") (name "Net-(U7-VCC)") (class "Default")
      (node (ref "C13") (pin "2") (pinfunction "2_2") (pintype "passive"))
      (node (ref "C14") (pin "2") (pinfunction "2_2") (pintype "passive"))
      (node (ref "L3") (pin "1") (pinfunction "1_1") (pintype "passive"))
      (node (ref "U7") (pin "8") (pinfunction "VCC_8") (pintype "passive"))
    )
    (net (code "79") (name "Net-(U7-VOUT)") (class "Default")
      (node (ref "R12") (pin "2") (pinfunction "2_2") (pintype "passive"))
      (node (ref "U7") (pin "7") (pinfunction "VOUT_7") (pintype "passive"))
    )
  )
)
